# nRF52810_qfaa_dcdc.net
KiCad netlist of a schematic drawn in EAGLE
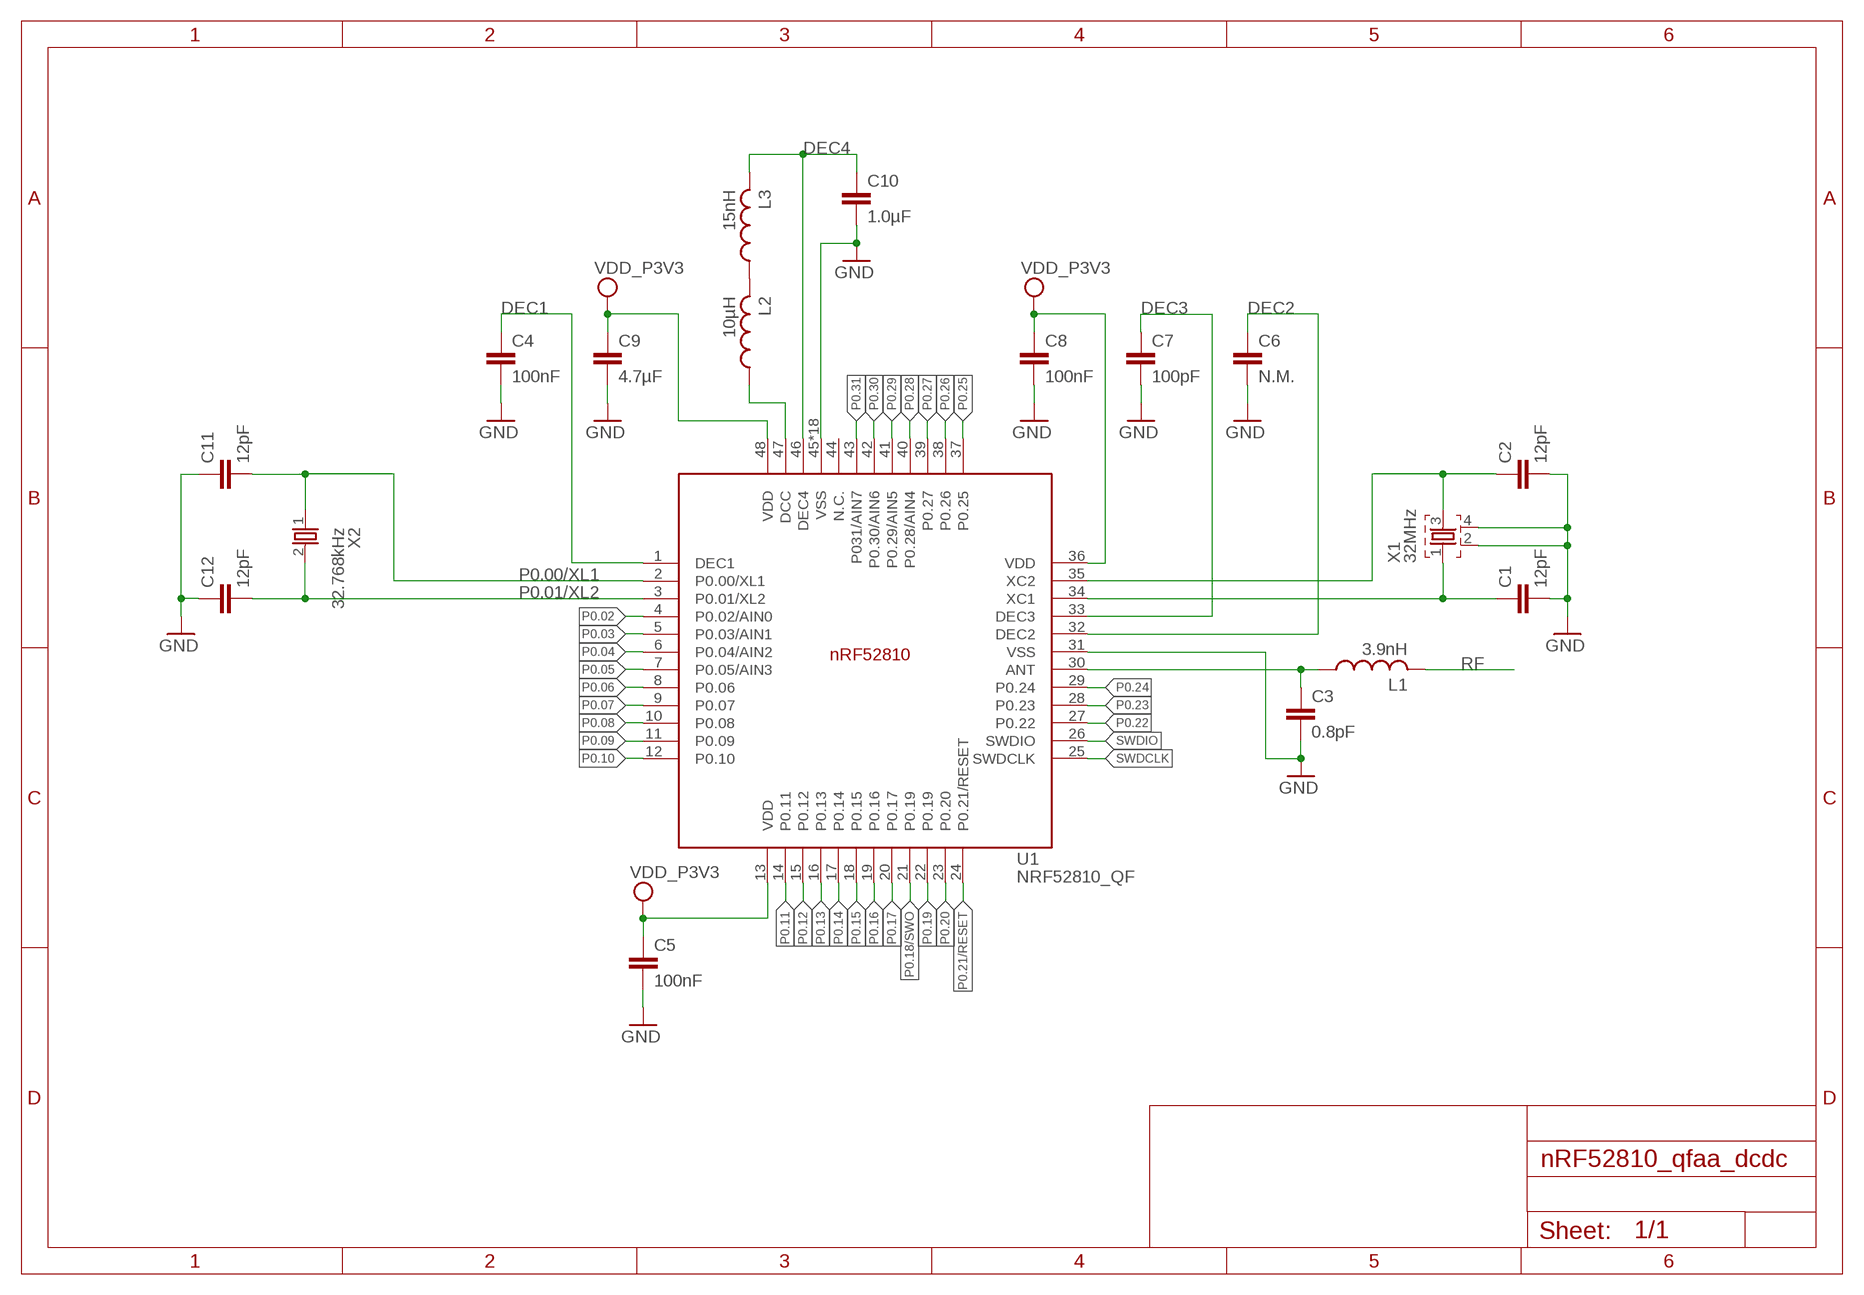
[diagram p0: schematic, sheet 1]

(export (version "E")
  (design (tool "Eeschema 10.0.6"))
  (components
    (comp (ref "C1")
      (value "12pF")
      (footprint "eagle-import:RESC0402_N")
      (libsource (lib "eagle-import") (part "CAPACITOR_0402_N"))
    )
    (comp (ref "C2")
      (value "12pF")
      (footprint "eagle-import:RESC0402_N")
      (libsource (lib "eagle-import") (part "CAPACITOR_0402_N"))
    )
    (comp (ref "C3")
      (value "0.8pF")
      (footprint "eagle-import:RESC0402_N")
      (libsource (lib "eagle-import") (part "CAPACITOR_0402_N"))
    )
    (comp (ref "C4")
      (value "100nF")
      (footprint "eagle-import:RESC0402_N")
      (libsource (lib "eagle-import") (part "CAPACITOR_0402_N"))
    )
    (comp (ref "C5")
      (value "100nF")
      (footprint "eagle-import:RESC0402_N")
      (libsource (lib "eagle-import") (part "CAPACITOR_0402_N"))
    )
    (comp (ref "C6")
      (value "N.M.")
      (footprint "eagle-import:RESC0402_N")
      (libsource (lib "eagle-import") (part "CAPACITOR_0402_N"))
    )
    (comp (ref "C7")
      (value "100pF")
      (footprint "eagle-import:RESC0402_N")
      (libsource (lib "eagle-import") (part "CAPACITOR_0402_N"))
    )
    (comp (ref "C8")
      (value "100nF")
      (footprint "eagle-import:RESC0402_N")
      (libsource (lib "eagle-import") (part "CAPACITOR_0402_N"))
    )
    (comp (ref "C9")
      (value "4.7µF")
      (footprint "eagle-import:RESC0603_N")
      (libsource (lib "eagle-import") (part "CAPACITOR_0603_N"))
    )
    (comp (ref "C10")
      (value "1.0µF")
      (footprint "eagle-import:RESC0603_N")
      (libsource (lib "eagle-import") (part "CAPACITOR_0603_N"))
    )
    (comp (ref "C11")
      (value "12pF")
      (footprint "eagle-import:RESC0402_N")
      (libsource (lib "eagle-import") (part "CAPACITOR_0402_N"))
    )
    (comp (ref "C12")
      (value "12pF")
      (footprint "eagle-import:RESC0402_N")
      (libsource (lib "eagle-import") (part "CAPACITOR_0402_N"))
    )
    (comp (ref "L1")
      (value "3.9nH")
      (footprint "eagle-import:RESC0402_N")
      (libsource (lib "eagle-import") (part "INDUCTOR_0402_N"))
    )
    (comp (ref "L2")
      (value "10µH")
      (footprint "eagle-import:RESC0603_N")
      (libsource (lib "eagle-import") (part "INDUCTOR_0603_N"))
    )
    (comp (ref "L3")
      (value "15nH")
      (footprint "eagle-import:RESC0402_N")
      (libsource (lib "eagle-import") (part "INDUCTOR_0402_N"))
    )
    (comp (ref "U1")
      (value "NRF52810_QF")
      (footprint "eagle-import:QFN40P600X600X90-48_N")
      (libsource (lib "eagle-import") (part "NRF52810_QF"))
    )
    (comp (ref "X1")
      (value "32MHz")
      (footprint "eagle-import:BT-XTAL_2016_N")
      (libsource (lib "eagle-import") (part "XTAL_32MHZ"))
    )
    (comp (ref "X2")
      (value "32.768kHz")
      (footprint "eagle-import:XTAL_3215_N")
      (libsource (lib "eagle-import") (part "XTAL_32KHZ"))
    )
  )
  (nets
    (net (code "1") (name "/DEC1") (class "Default")
      (node (ref "C4") (pin "1") (pinfunction "1_1") (pintype "passive"))
      (node (ref "U1") (pin "1") (pinfunction "DEC1_1") (pintype "bidirectional"))
    )
    (net (code "2") (name "/DEC2") (class "Default")
      (node (ref "C6") (pin "1") (pinfunction "1_1") (pintype "passive"))
      (node (ref "U1") (pin "32") (pinfunction "DEC2_32") (pintype "bidirectional"))
    )
    (net (code "3") (name "/DEC3") (class "Default")
      (node (ref "C7") (pin "1") (pinfunction "1_1") (pintype "passive"))
      (node (ref "U1") (pin "33") (pinfunction "DEC3_33") (pintype "bidirectional"))
    )
    (net (code "4") (name "/DEC4") (class "Default")
      (node (ref "C10") (pin "1") (pinfunction "1_1") (pintype "passive"))
      (node (ref "L3") (pin "2") (pinfunction "2_2") (pintype "passive"))
      (node (ref "U1") (pin "46") (pinfunction "DEC4_46") (pintype "bidirectional"))
    )
    (net (code "5") (name "/P0.00{slash}XL1") (class "Default")
      (node (ref "C11") (pin "2") (pinfunction "2_2") (pintype "passive"))
      (node (ref "U1") (pin "2") (pinfunction "P0.00/XL1_2") (pintype "bidirectional"))
      (node (ref "X2") (pin "1") (pinfunction "1_1") (pintype "passive"))
    )
    (net (code "6") (name "/P0.01{slash}XL2") (class "Default")
      (node (ref "C12") (pin "2") (pinfunction "2_2") (pintype "passive"))
      (node (ref "U1") (pin "3") (pinfunction "P0.01/XL2_3") (pintype "bidirectional"))
      (node (ref "X2") (pin "2") (pinfunction "2_2") (pintype "passive"))
    )
    (net (code "7") (name "/RF") (class "Default")
      (node (ref "L1") (pin "2") (pinfunction "2_2") (pintype "passive"))
    )
    (net (code "8") (name "GND") (class "Default")
      (node (ref "C1") (pin "2") (pinfunction "2_2") (pintype "passive"))
      (node (ref "C10") (pin "2") (pinfunction "2_2") (pintype "passive"))
      (node (ref "C11") (pin "1") (pinfunction "1_1") (pintype "passive"))
      (node (ref "C12") (pin "1") (pinfunction "1_1") (pintype "passive"))
      (node (ref "C2") (pin "2") (pinfunction "2_2") (pintype "passive"))
      (node (ref "C3") (pin "2") (pinfunction "2_2") (pintype "passive"))
      (node (ref "C4") (pin "2") (pinfunction "2_2") (pintype "passive"))
      (node (ref "C5") (pin "2") (pinfunction "2_2") (pintype "passive"))
      (node (ref "C6") (pin "2") (pinfunction "2_2") (pintype "passive"))
      (node (ref "C7") (pin "2") (pinfunction "2_2") (pintype "passive"))
      (node (ref "C8") (pin "2") (pinfunction "2_2") (pintype "passive"))
      (node (ref "C9") (pin "2") (pinfunction "2_2") (pintype "passive"))
      (node (ref "U1") (pin "31") (pinfunction "VSS_31") (pintype "bidirectional"))
      (node (ref "U1") (pin "45") (pinfunction "VSS_45") (pintype "bidirectional"))
      (node (ref "U1") (pin "PAD") (pinfunction "VSS_PAD") (pintype "bidirectional"))
      (node (ref "U1") (pin "PAD@VIA01") (pinfunction "VSS_PAD@VIA01") (pintype "bidirectional"))
      (node (ref "U1") (pin "PAD@VIA02") (pinfunction "VSS_PAD@VIA02") (pintype "bidirectional"))
      (node (ref "U1") (pin "PAD@VIA03") (pinfunction "VSS_PAD@VIA03") (pintype "bidirectional"))
      (node (ref "U1") (pin "PAD@VIA04") (pinfunction "VSS_PAD@VIA04") (pintype "bidirectional"))
      (node (ref "U1") (pin "PAD@VIA05") (pinfunction "VSS_PAD@VIA05") (pintype "bidirectional"))
      (node (ref "U1") (pin "PAD@VIA06") (pinfunction "VSS_PAD@VIA06") (pintype "bidirectional"))
      (node (ref "U1") (pin "PAD@VIA07") (pinfunction "VSS_PAD@VIA07") (pintype "bidirectional"))
      (node (ref "U1") (pin "PAD@VIA08") (pinfunction "VSS_PAD@VIA08") (pintype "bidirectional"))
      (node (ref "U1") (pin "PAD@VIA09") (pinfunction "VSS_PAD@VIA09") (pintype "bidirectional"))
      (node (ref "U1") (pin "PAD@VIA10") (pinfunction "VSS_PAD@VIA10") (pintype "bidirectional"))
      (node (ref "U1") (pin "PAD@VIA11") (pinfunction "VSS_PAD@VIA11") (pintype "bidirectional"))
      (node (ref "U1") (pin "PAD@VIA12") (pinfunction "VSS_PAD@VIA12") (pintype "bidirectional"))
      (node (ref "U1") (pin "PAD@VIA13") (pinfunction "VSS_PAD@VIA13") (pintype "bidirectional"))
      (node (ref "U1") (pin "PAD@VIA14") (pinfunction "VSS_PAD@VIA14") (pintype "bidirectional"))
      (node (ref "U1") (pin "PAD@VIA15") (pinfunction "VSS_PAD@VIA15") (pintype "bidirectional"))
      (node (ref "U1") (pin "PAD@VIA16") (pinfunction "VSS_PAD@VIA16") (pintype "bidirectional"))
      (node (ref "X1") (pin "2") (pinfunction "2_2") (pintype "passive"))
      (node (ref "X1") (pin "4") (pinfunction "4_4") (pintype "passive"))
    )
    (net (code "9") (name "Net-(L2-Pad2)") (class "Default")
      (node (ref "L2") (pin "2") (pinfunction "2_2") (pintype "passive"))
      (node (ref "L3") (pin "1") (pinfunction "1_1") (pintype "passive"))
    )
    (net (code "10") (name "Net-(U1-ANT)") (class "Default")
      (node (ref "C3") (pin "1") (pinfunction "1_1") (pintype "passive"))
      (node (ref "L1") (pin "1") (pinfunction "1_1") (pintype "passive"))
      (node (ref "U1") (pin "30") (pinfunction "ANT_30") (pintype "bidirectional"))
    )
    (net (code "11") (name "Net-(U1-DCC)") (class "Default")
      (node (ref "L2") (pin "1") (pinfunction "1_1") (pintype "passive"))
      (node (ref "U1") (pin "47") (pinfunction "DCC_47") (pintype "bidirectional"))
    )
    (net (code "12") (name "Net-(U1-XC1)") (class "Default")
      (node (ref "C1") (pin "1") (pinfunction "1_1") (pintype "passive"))
      (node (ref "U1") (pin "34") (pinfunction "XC1_34") (pintype "bidirectional"))
      (node (ref "X1") (pin "1") (pinfunction "1_1") (pintype "passive"))
    )
    (net (code "13") (name "Net-(U1-XC2)") (class "Default")
      (node (ref "C2") (pin "1") (pinfunction "1_1") (pintype "passive"))
      (node (ref "U1") (pin "35") (pinfunction "XC2_35") (pintype "bidirectional"))
      (node (ref "X1") (pin "3") (pinfunction "3_3") (pintype "passive"))
    )
    (net (code "14") (name "P0.02") (class "Default")
      (node (ref "U1") (pin "4") (pinfunction "P0.02/AIN0_4") (pintype "bidirectional"))
    )
    (net (code "15") (name "P0.03") (class "Default")
      (node (ref "U1") (pin "5") (pinfunction "P0.03/AIN1_5") (pintype "bidirectional"))
    )
    (net (code "16") (name "P0.04") (class "Default")
      (node (ref "U1") (pin "6") (pinfunction "P0.04/AIN2_6") (pintype "bidirectional"))
    )
    (net (code "17") (name "P0.05") (class "Default")
      (node (ref "U1") (pin "7") (pinfunction "P0.05/AIN3_7") (pintype "bidirectional"))
    )
    (net (code "18") (name "P0.06") (class "Default")
      (node (ref "U1") (pin "8") (pinfunction "P0.06_8") (pintype "bidirectional"))
    )
    (net (code "19") (name "P0.07") (class "Default")
      (node (ref "U1") (pin "9") (pinfunction "P0.07_9") (pintype "bidirectional"))
    )
    (net (code "20") (name "P0.08") (class "Default")
      (node (ref "U1") (pin "10") (pinfunction "P0.08_10") (pintype "bidirectional"))
    )
    (net (code "21") (name "P0.09") (class "Default")
      (node (ref "U1") (pin "11") (pinfunction "P0.09_11") (pintype "bidirectional"))
    )
    (net (code "22") (name "P0.10") (class "Default")
      (node (ref "U1") (pin "12") (pinfunction "P0.10_12") (pintype "bidirectional"))
    )
    (net (code "23") (name "P0.11") (class "Default")
      (node (ref "U1") (pin "14") (pinfunction "P0.11_14") (pintype "bidirectional"))
    )
    (net (code "24") (name "P0.12") (class "Default")
      (node (ref "U1") (pin "15") (pinfunction "P0.12_15") (pintype "bidirectional"))
    )
    (net (code "25") (name "P0.13") (class "Default")
      (node (ref "U1") (pin "16") (pinfunction "P0.13_16") (pintype "bidirectional"))
    )
    (net (code "26") (name "P0.14") (class "Default")
      (node (ref "U1") (pin "17") (pinfunction "P0.14_17") (pintype "bidirectional"))
    )
    (net (code "27") (name "P0.15") (class "Default")
      (node (ref "U1") (pin "18") (pinfunction "P0.15_18") (pintype "bidirectional"))
    )
    (net (code "28") (name "P0.16") (class "Default")
      (node (ref "U1") (pin "19") (pinfunction "P0.16_19") (pintype "bidirectional"))
    )
    (net (code "29") (name "P0.17") (class "Default")
      (node (ref "U1") (pin "20") (pinfunction "P0.17_20") (pintype "bidirectional"))
    )
    (net (code "30") (name "P0.18{slash}SWO") (class "Default")
      (node (ref "U1") (pin "21") (pinfunction "P0.19_21") (pintype "bidirectional"))
    )
    (net (code "31") (name "P0.19") (class "Default")
      (node (ref "U1") (pin "22") (pinfunction "P0.19_22") (pintype "bidirectional"))
    )
    (net (code "32") (name "P0.20") (class "Default")
      (node (ref "U1") (pin "23") (pinfunction "P0.20_23") (pintype "bidirectional"))
    )
    (net (code "33") (name "P0.21{slash}RESET") (class "Default")
      (node (ref "U1") (pin "24") (pinfunction "P0.21/RESET_24") (pintype "bidirectional"))
    )
    (net (code "34") (name "P0.22") (class "Default")
      (node (ref "U1") (pin "27") (pinfunction "P0.22_27") (pintype "bidirectional"))
    )
    (net (code "35") (name "P0.23") (class "Default")
      (node (ref "U1") (pin "28") (pinfunction "P0.23_28") (pintype "bidirectional"))
    )
    (net (code "36") (name "P0.24") (class "Default")
      (node (ref "U1") (pin "29") (pinfunction "P0.24_29") (pintype "bidirectional"))
    )
    (net (code "37") (name "P0.25") (class "Default")
      (node (ref "U1") (pin "37") (pinfunction "P0.25_37") (pintype "bidirectional"))
    )
    (net (code "38") (name "P0.26") (class "Default")
      (node (ref "U1") (pin "38") (pinfunction "P0.26_38") (pintype "bidirectional"))
    )
    (net (code "39") (name "P0.27") (class "Default")
      (node (ref "U1") (pin "39") (pinfunction "P0.27_39") (pintype "bidirectional"))
    )
    (net (code "40") (name "P0.28") (class "Default")
      (node (ref "U1") (pin "40") (pinfunction "P0.28/AIN4_40") (pintype "bidirectional"))
    )
    (net (code "41") (name "P0.29") (class "Default")
      (node (ref "U1") (pin "41") (pinfunction "P0.29/AIN5_41") (pintype "bidirectional"))
    )
    (net (code "42") (name "P0.30") (class "Default")
      (node (ref "U1") (pin "42") (pinfunction "P0.30/AIN6_42") (pintype "bidirectional"))
    )
    (net (code "43") (name "P0.31") (class "Default")
      (node (ref "U1") (pin "43") (pinfunction "P031/AIN7_43") (pintype "bidirectional"))
    )
    (net (code "44") (name "SWDCLK") (class "Default")
      (node (ref "U1") (pin "25") (pinfunction "SWDCLK_25") (pintype "bidirectional"))
    )
    (net (code "45") (name "SWDIO") (class "Default")
      (node (ref "U1") (pin "26") (pinfunction "SWDIO_26") (pintype "bidirectional"))
    )
    (net (code "46") (name "VDD_P3V3") (class "Default")
      (node (ref "C5") (pin "1") (pinfunction "1_1") (pintype "passive"))
      (node (ref "C8") (pin "1") (pinfunction "1_1") (pintype "passive"))
      (node (ref "C9") (pin "1") (pinfunction "1_1") (pintype "passive"))
      (node (ref "U1") (pin "13") (pinfunction "VDD_13") (pintype "bidirectional"))
      (node (ref "U1") (pin "36") (pinfunction "VDD_36") (pintype "bidirectional"))
      (node (ref "U1") (pin "48") (pinfunction "VDD_48") (pintype "bidirectional"))
    )
    (net (code "47") (name "unconnected-(U1-N.C.-Pad44)") (class "Default")
      (node (ref "U1") (pin "44") (pinfunction "N.C._44") (pintype "bidirectional"))
    )
  )
)
